# nice_view_dongle.net
KiCad netlist of a schematic drawn in EasyEDA Pro
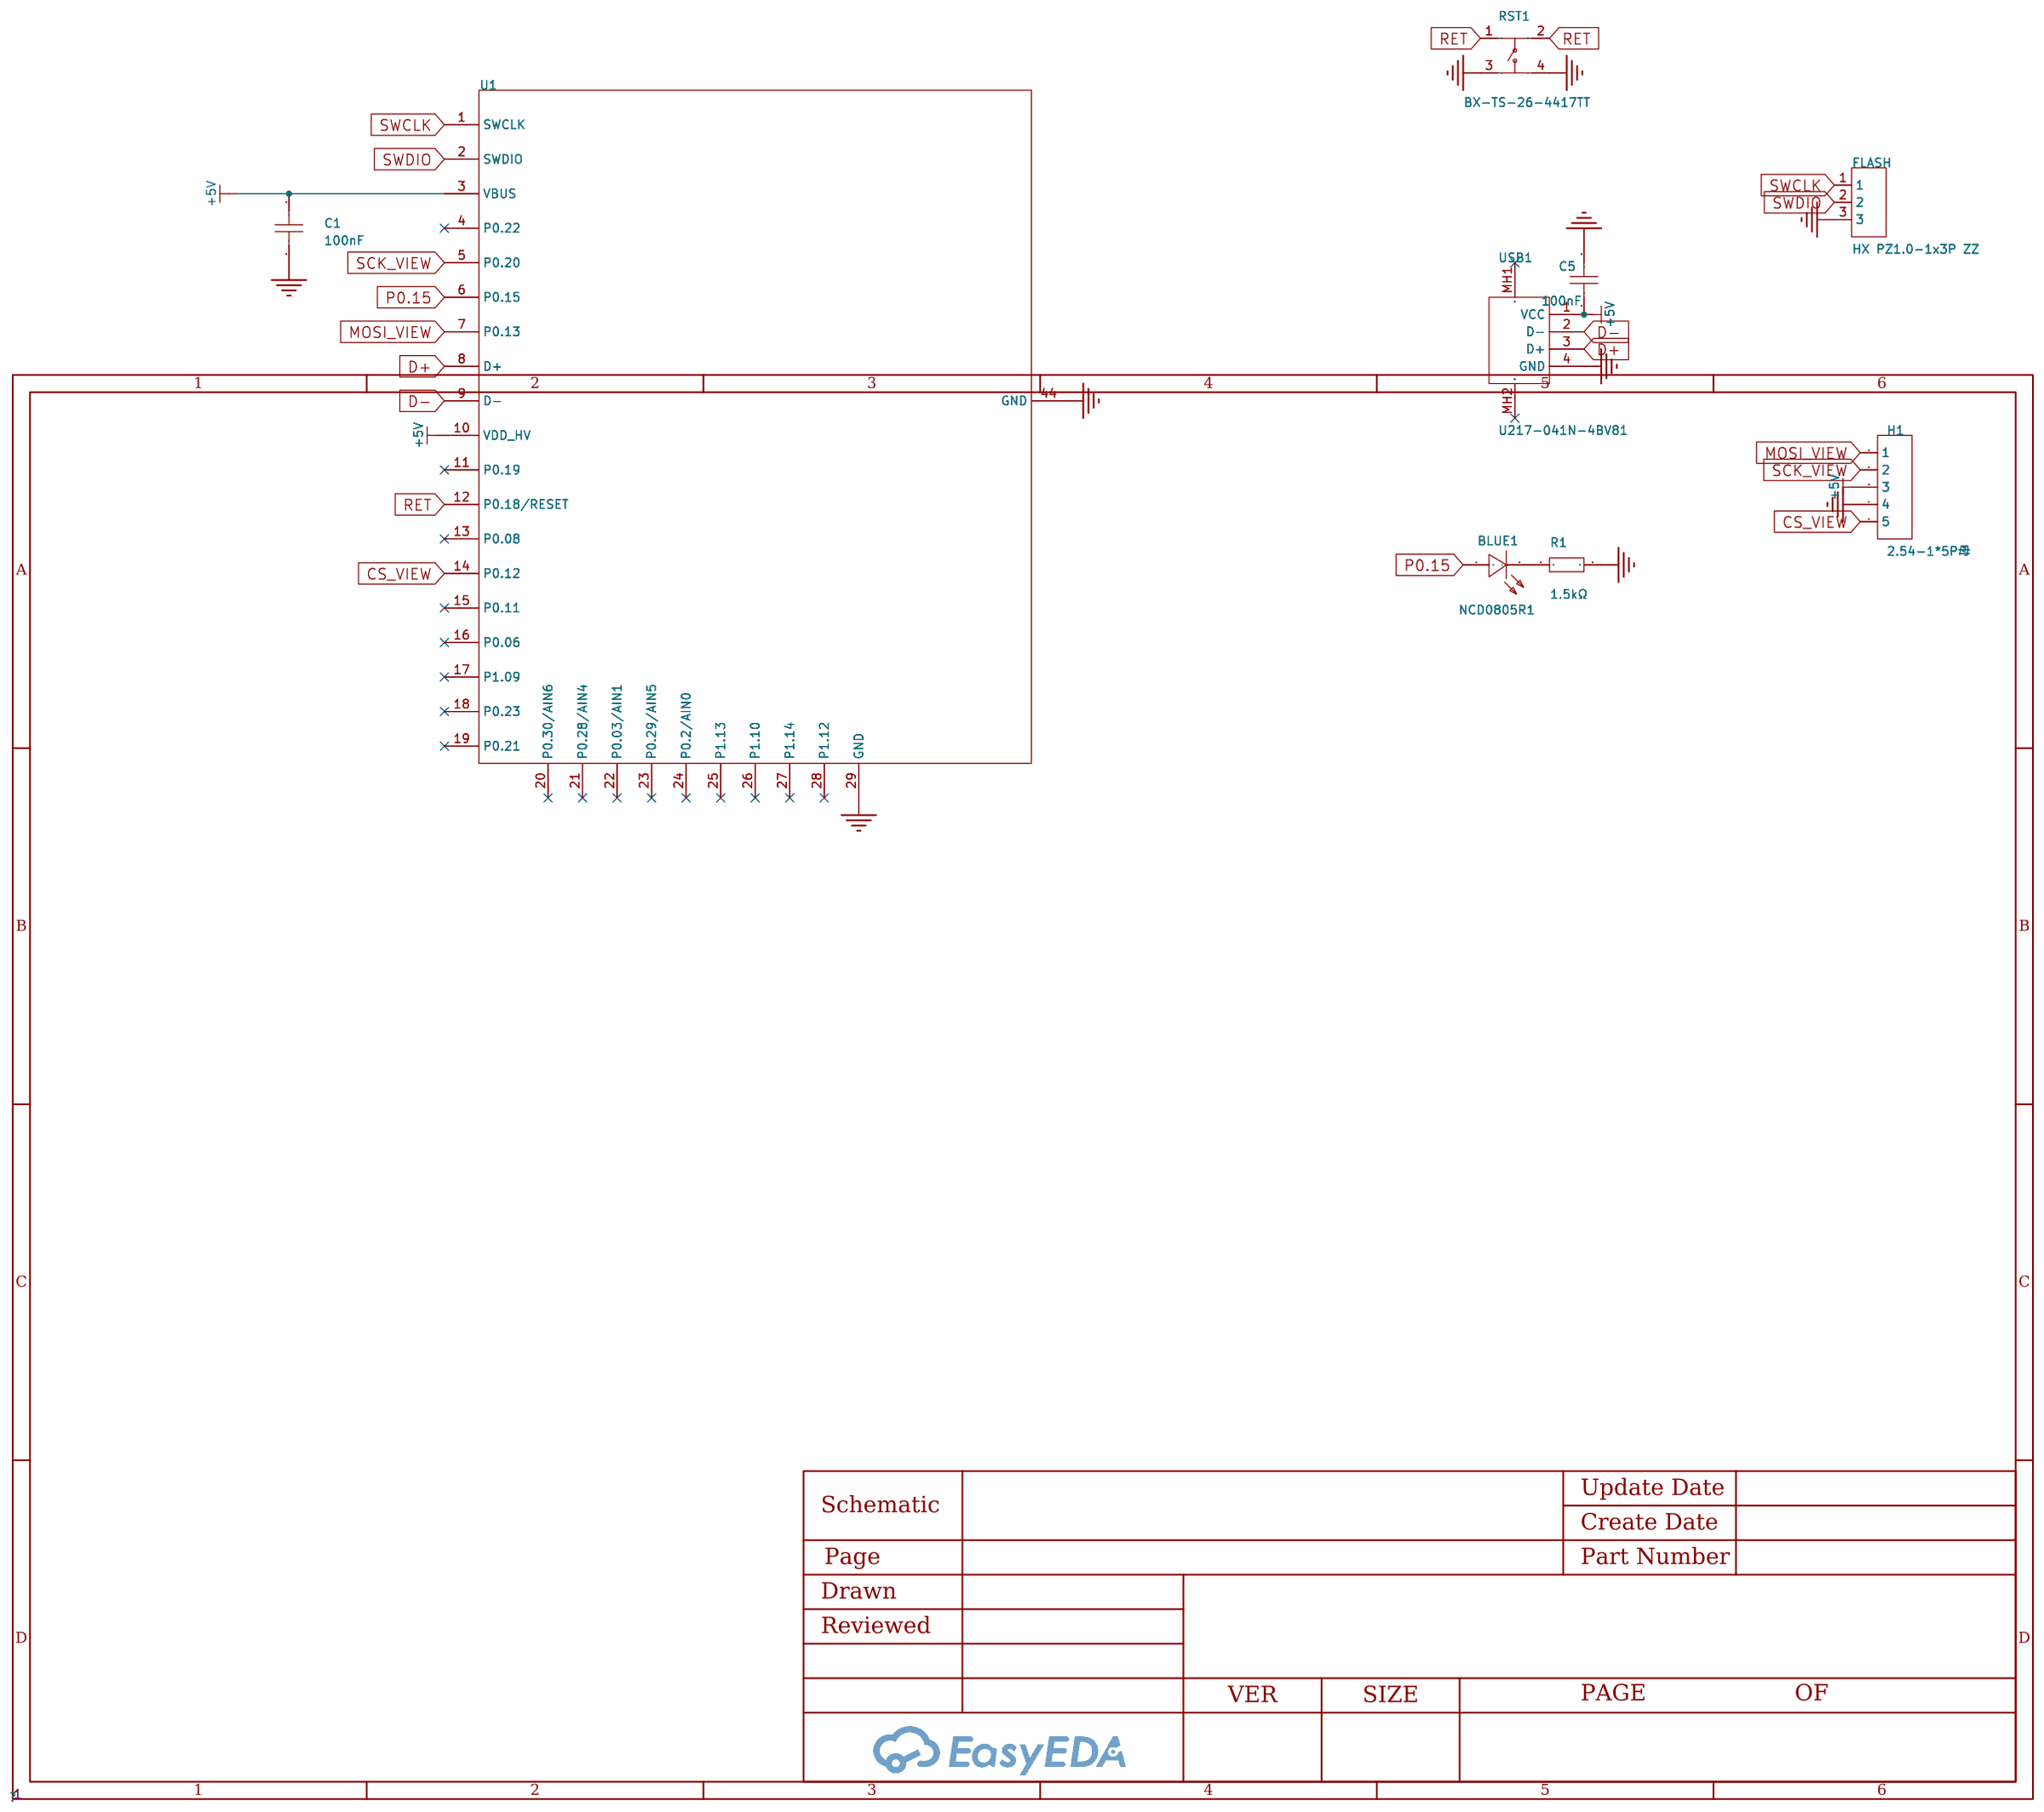
[diagram p0: schematic sheet]

(export (version "E")
  (design (tool "Eeschema 10.0.6"))
  (components
    (comp (ref "BLUE1")
      (value "NCD0805R1")
      (footprint "easyedapro:LED0805-R-RD")
      (fields (field (name "Manufacturer") "国星光电"))
      (libsource (lib "easyedapro") (part "FC-2012HRK-620D"))
    )
    (comp (ref "C1")
      (value "100nF")
      (footprint "easyedapro:C0603")
      (libsource (lib "easyedapro") (part "CapAcitance"))
    )
    (comp (ref "C5")
      (value "100nF")
      (footprint "easyedapro:C0603")
      (fields
        (field (name "Manufacturer Part") "CGA0603X7R104K500JT")
        (field (name "Manufacturer") "HRE(芯声)")
      )
      (libsource (lib "easyedapro") (part "CapAcitance"))
    )
    (comp (ref "FLASH")
      (value "HX PZ1.0-1x3P ZZ")
      (fields (field (name "Manufacturer") "hanxia(韩下)"))
      (libsource (lib "easyedapro") (part "PZ254V-11-03P_C2937625"))
    )
    (comp (ref "H1")
      (value "2.54-1*5P母")
      (footprint "easyedapro:HDR-TH_5P-P2.54-V-F")
      (description "插孔结构:1x5P;间距:2.54mm;行距:-;安装类型:直插;排数:单排;总孔位数:5P;塑高:-;触头材质:-;触头镀层:-;")
      (fields (field (name "Manufacturer") "BOOMELE(博穆精密)"))
      (libsource (lib "easyedapro") (part "Header-Female-2.54_1x5"))
    )
    (comp (ref "R1")
      (value "1.5kΩ")
      (fields (field (name "Manufacturer Part") "FRC1206J152 TS") (field (name "Manufacturer") "FOJAN(富捷)"))
      (libsource (lib "easyedapro") (part "0805W8F1501T5E"))
    )
    (comp (ref "RST1")
      (value "BX-TS-26-4417TT")
      (footprint "easyedapro:SW-SMD_4P-L5.2-W5.2-P3.70-LS6.5")
      (fields (field (name "Manufacturer") "Bossie(博锡)"))
      (libsource (lib "easyedapro") (part "BX-TS-26-4417TT"))
    )
    (comp (ref "U1")
      (value "N52840")
      (footprint "easyedapro:52840MICRO-v1")
      (libsource (lib "easyedapro") (part "52840micro"))
    )
    (comp (ref "USB1")
      (value "U217-041N-4BV81")
      (fields (field (name "Manufacturer") "XKB Connection(中国星坤)"))
      (libsource (lib "easyedapro") (part "AM90"))
    )
  )
  (nets
    (net (code "1") (name "+5V") (class "Default")
      (node (ref "C1") (pin "2") (pinfunction "2_2") (pintype "input"))
      (node (ref "C5") (pin "1") (pinfunction "1_1") (pintype "input"))
      (node (ref "H1") (pin "3") (pinfunction "3_3") (pintype "input"))
      (node (ref "U1") (pin "10") (pinfunction "VDD_HV_10") (pintype "input"))
      (node (ref "U1") (pin "3") (pinfunction "VBUS_3") (pintype "input"))
      (node (ref "USB1") (pin "1") (pinfunction "VCC_1") (pintype "input"))
    )
    (net (code "2") (name "CS_VIEW") (class "Default")
      (node (ref "H1") (pin "5") (pinfunction "5_5") (pintype "input"))
      (node (ref "U1") (pin "14") (pinfunction "P0.12_14") (pintype "input"))
    )
    (net (code "3") (name "D+") (class "Default")
      (node (ref "U1") (pin "8") (pinfunction "D+_8") (pintype "input"))
      (node (ref "USB1") (pin "3") (pinfunction "D+_3") (pintype "input"))
    )
    (net (code "4") (name "D-") (class "Default")
      (node (ref "U1") (pin "9") (pinfunction "D-_9") (pintype "input"))
      (node (ref "USB1") (pin "2") (pinfunction "D-_2") (pintype "input"))
    )
    (net (code "5") (name "GND") (class "Default")
      (node (ref "C1") (pin "1") (pinfunction "1_1") (pintype "input"))
      (node (ref "C5") (pin "2") (pinfunction "2_2") (pintype "input"))
      (node (ref "FLASH") (pin "3") (pinfunction "3_3") (pintype "unspecified"))
      (node (ref "H1") (pin "4") (pinfunction "4_4") (pintype "input"))
      (node (ref "R1") (pin "2") (pinfunction "2_2") (pintype "input"))
      (node (ref "RST1") (pin "3") (pinfunction "3_3") (pintype "unspecified"))
      (node (ref "RST1") (pin "4") (pinfunction "4_4") (pintype "unspecified"))
      (node (ref "U1") (pin "29") (pinfunction "GND_29") (pintype "input"))
      (node (ref "U1") (pin "44") (pinfunction "GND_44") (pintype "input"))
      (node (ref "USB1") (pin "4") (pinfunction "GND_4") (pintype "input"))
    )
    (net (code "6") (name "MOSI_VIEW") (class "Default")
      (node (ref "H1") (pin "1") (pinfunction "1_1") (pintype "input"))
      (node (ref "U1") (pin "7") (pinfunction "P0.13_7") (pintype "input"))
    )
    (net (code "7") (name "Net-(BLUE1--)") (class "Default")
      (node (ref "BLUE1") (pin "2") (pinfunction "-_2") (pintype "unspecified"))
      (node (ref "R1") (pin "1") (pinfunction "1_1") (pintype "input"))
    )
    (net (code "8") (name "P0.15") (class "Default")
      (node (ref "BLUE1") (pin "1") (pinfunction "+_1") (pintype "unspecified"))
      (node (ref "U1") (pin "6") (pinfunction "P0.15_6") (pintype "input"))
    )
    (net (code "9") (name "RET") (class "Default")
      (node (ref "RST1") (pin "1") (pinfunction "1_1") (pintype "unspecified"))
      (node (ref "RST1") (pin "2") (pinfunction "2_2") (pintype "unspecified"))
      (node (ref "U1") (pin "12") (pinfunction "P0.18/RESET_12") (pintype "input"))
    )
    (net (code "10") (name "SCK_VIEW") (class "Default")
      (node (ref "H1") (pin "2") (pinfunction "2_2") (pintype "input"))
      (node (ref "U1") (pin "5") (pinfunction "P0.20_5") (pintype "input"))
    )
    (net (code "11") (name "SWCLK") (class "Default")
      (node (ref "FLASH") (pin "1") (pinfunction "1_1") (pintype "unspecified"))
      (node (ref "U1") (pin "1") (pinfunction "SWCLK_1") (pintype "input"))
    )
    (net (code "12") (name "SWDIO") (class "Default")
      (node (ref "FLASH") (pin "2") (pinfunction "2_2") (pintype "unspecified"))
      (node (ref "U1") (pin "2") (pinfunction "SWDIO_2") (pintype "input"))
    )
    (net (code "13") (name "unconnected-(U1-P0.2{slash}AIN0-Pad24)") (class "Default")
      (node (ref "U1") (pin "24") (pinfunction "P0.2/AIN0_24") (pintype "input+no_connect"))
    )
    (net (code "14") (name "unconnected-(U1-P0.03{slash}AIN1-Pad22)") (class "Default")
      (node (ref "U1") (pin "22") (pinfunction "P0.03/AIN1_22") (pintype "input+no_connect"))
    )
    (net (code "15") (name "unconnected-(U1-P0.06-Pad16)") (class "Default")
      (node (ref "U1") (pin "16") (pinfunction "P0.06_16") (pintype "input+no_connect"))
    )
    (net (code "16") (name "unconnected-(U1-P0.08-Pad13)") (class "Default")
      (node (ref "U1") (pin "13") (pinfunction "P0.08_13") (pintype "input+no_connect"))
    )
    (net (code "17") (name "unconnected-(U1-P0.11-Pad15)") (class "Default")
      (node (ref "U1") (pin "15") (pinfunction "P0.11_15") (pintype "input+no_connect"))
    )
    (net (code "18") (name "unconnected-(U1-P0.19-Pad11)") (class "Default")
      (node (ref "U1") (pin "11") (pinfunction "P0.19_11") (pintype "input+no_connect"))
    )
    (net (code "19") (name "unconnected-(U1-P0.21-Pad19)") (class "Default")
      (node (ref "U1") (pin "19") (pinfunction "P0.21_19") (pintype "input+no_connect"))
    )
    (net (code "20") (name "unconnected-(U1-P0.22-Pad4)") (class "Default")
      (node (ref "U1") (pin "4") (pinfunction "P0.22_4") (pintype "input+no_connect"))
    )
    (net (code "21") (name "unconnected-(U1-P0.23-Pad18)") (class "Default")
      (node (ref "U1") (pin "18") (pinfunction "P0.23_18") (pintype "input+no_connect"))
    )
    (net (code "22") (name "unconnected-(U1-P0.28{slash}AIN4-Pad21)") (class "Default")
      (node (ref "U1") (pin "21") (pinfunction "P0.28/AIN4_21") (pintype "input+no_connect"))
    )
    (net (code "23") (name "unconnected-(U1-P0.29{slash}AIN5-Pad23)") (class "Default")
      (node (ref "U1") (pin "23") (pinfunction "P0.29/AIN5_23") (pintype "input+no_connect"))
    )
    (net (code "24") (name "unconnected-(U1-P0.30{slash}AIN6-Pad20)") (class "Default")
      (node (ref "U1") (pin "20") (pinfunction "P0.30/AIN6_20") (pintype "input+no_connect"))
    )
    (net (code "25") (name "unconnected-(U1-P1.09-Pad17)") (class "Default")
      (node (ref "U1") (pin "17") (pinfunction "P1.09_17") (pintype "input+no_connect"))
    )
    (net (code "26") (name "unconnected-(U1-P1.10-Pad26)") (class "Default")
      (node (ref "U1") (pin "26") (pinfunction "P1.10_26") (pintype "input+no_connect"))
    )
    (net (code "27") (name "unconnected-(U1-P1.12-Pad28)") (class "Default")
      (node (ref "U1") (pin "28") (pinfunction "P1.12_28") (pintype "input+no_connect"))
    )
    (net (code "28") (name "unconnected-(U1-P1.13-Pad25)") (class "Default")
      (node (ref "U1") (pin "25") (pinfunction "P1.13_25") (pintype "input+no_connect"))
    )
    (net (code "29") (name "unconnected-(U1-P1.14-Pad27)") (class "Default")
      (node (ref "U1") (pin "27") (pinfunction "P1.14_27") (pintype "input+no_connect"))
    )
    (net (code "30") (name "unconnected-(USB1-PadMH1)") (class "Default")
      (node (ref "USB1") (pin "MH1") (pinfunction "MH1_MH1") (pintype "unspecified+no_connect"))
    )
    (net (code "31") (name "unconnected-(USB1-PadMH2)") (class "Default")
      (node (ref "USB1") (pin "MH2") (pinfunction "MH2_MH2") (pintype "unspecified+no_connect"))
    )
  )
)
